# Balance_batt_protection.net
KiCad netlist of a schematic drawn in Altium Designer
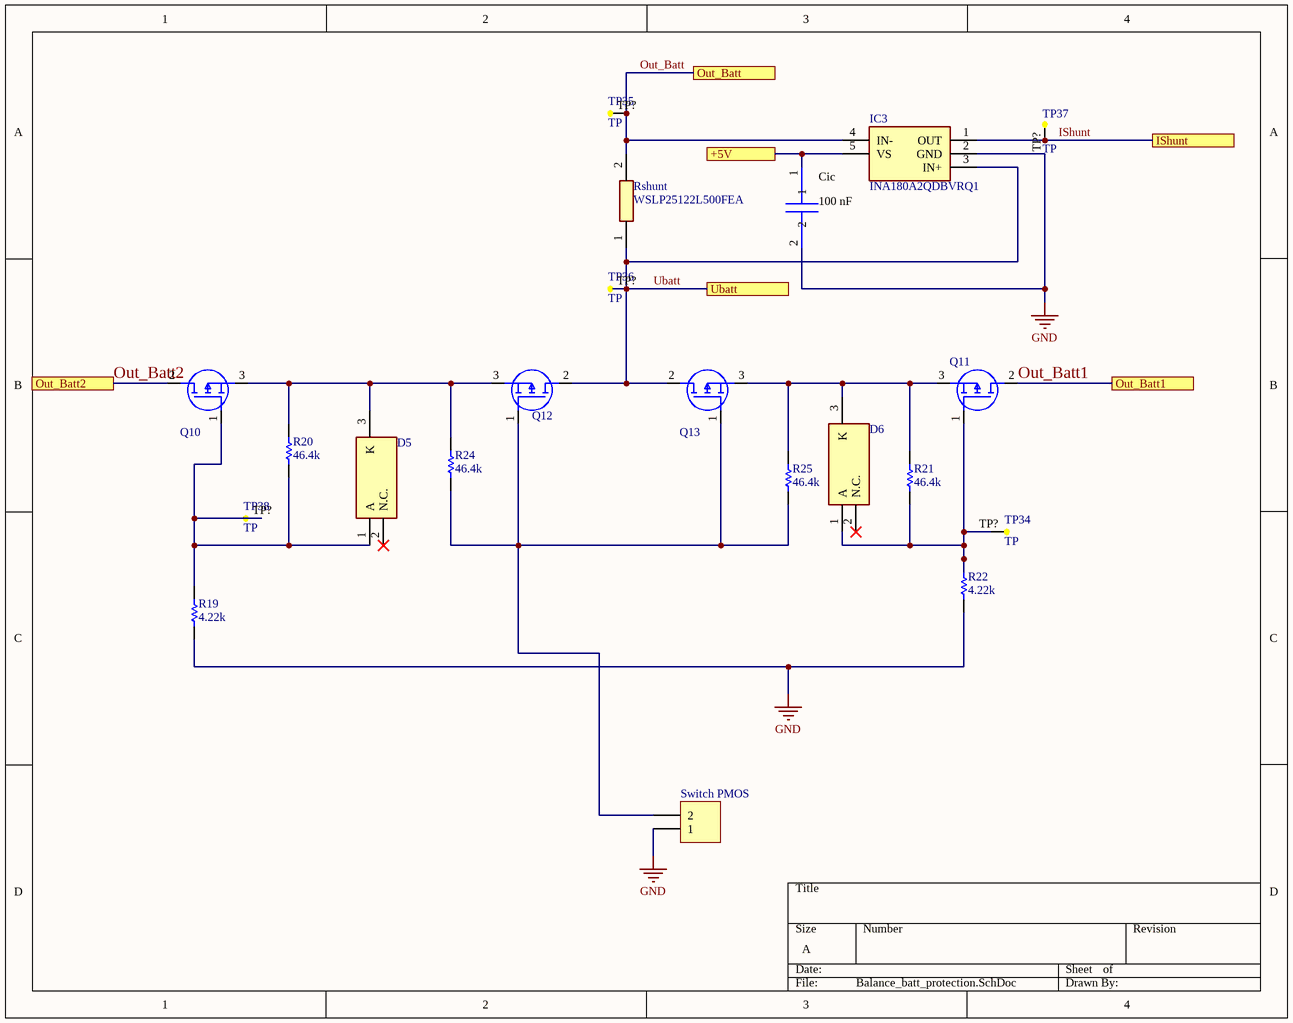
[diagram p0: Balance_batt_protection.SchDoc]

(export (version "E")
  (design (tool "Eeschema 10.0.6"))
  (components
    (comp (ref "Cic")
      (value "100 nF")
      (footprint "CAPC1005X55N")
      (description "C3216X6S1V106K16")
      (fields
        (field (name "MANUFACTURER PART NUMBER") "C3216X6S1V106K160AC")
        (field (name "Comment") "C2012X7S1C106K")
      )
      (libsource (lib "TI WEBENCH") (part "Cin"))
    )
    (comp (ref "D5")
      (value "SZBZX84C18ET1G")
      (footprint "SOT95P230X110-3N")
      (description "Zener Diode")
      (fields
        (field (name "MANUFACTURER_PART_NUMBER") "BZX84W-C15F")
        (field (name "MOUSER PART NUMBER") "771-BZX84W-C15F")
      )
      (libsource (lib "BZX84(sot 23)") (part "BZX84W-C15F"))
    )
    (comp (ref "D6")
      (value "SZBZX84C18ET1G")
      (footprint "SOT95P230X110-3N")
      (description "Zener Diode")
      (fields
        (field (name "MANUFACTURER_PART_NUMBER") "BZX84W-C15F")
        (field (name "MOUSER PART NUMBER") "771-BZX84W-C15F")
      )
      (libsource (lib "BZX84(sot 23)") (part "BZX84W-C15F"))
    )
    (comp (ref "IC3")
      (value "INA180A2QDBVRQ1")
      (footprint "SOT95P280X145-5N")
      (description "Attenuator or Isolator")
      (fields (field (name "MOUSER PART NUMBER") "595-INA180A2QDBVRQ1"))
      (libsource (lib "INA180A2QDBVRQ1") (part "INA180A2QDBVRQ1"))
    )
    (comp (ref "Q10")
      (value "SQD50P04-09L_GE3")
      (footprint "SamacSys:SQD50P0409L_GE3")
      (description "MOSFET (P-Channel)")
      (fields (field (name "MOUSER PART NUMBER") "78-SQD50P04-09L_GE3"))
      (libsource (lib "SQD50P04-09L_GE3(TO252)") (part "SQD50P04-09L_GE3"))
    )
    (comp (ref "Q11")
      (value "SQD50P04-09L_GE3")
      (footprint "SamacSys:SQD50P0409L_GE3")
      (description "MOSFET (P-Channel)")
      (fields (field (name "MOUSER PART NUMBER") "78-SQD50P04-09L_GE3"))
      (libsource (lib "SQD50P04-09L_GE3(TO252)") (part "SQD50P04-09L_GE3"))
    )
    (comp (ref "Q12")
      (value "SQD50P04-09L_GE3")
      (footprint "SQD50P0409L_GE3")
      (description "MOSFET (P-Channel)")
      (fields (field (name "MOUSER PART NUMBER") "78-SQD50P04-09L_GE3"))
      (libsource (lib "SQD50P04-09L_GE3(TO252)") (part "SQD50P04-09L_GE3"))
    )
    (comp (ref "Q13")
      (value "SQD50P04-09L_GE3")
      (footprint "SQD50P0409L_GE3")
      (description "MOSFET (P-Channel)")
      (fields (field (name "MOUSER PART NUMBER") "78-SQD50P04-09L_GE3"))
      (libsource (lib "SQD50P04-09L_GE3(TO252)") (part "SQD50P04-09L_GE3"))
    )
    (comp (ref "R19")
      (value "4.22k")
      (footprint "ERJP06D1000V")
      (description "Resistor")
      (fields (field (name "Comment") "MCR03..PFX1002") (field (name "PUBLISHER") "Altium Limited"))
      (libsource (lib "Miscellaneous Devices") (part "Res1"))
    )
    (comp (ref "R20")
      (value "46.4k")
      (footprint "RESC1608X55N")
      (description "Resistor")
      (fields (field (name "Comment") "MCR03..PFX1002") (field (name "PUBLISHER") "Altium Limited"))
      (libsource (lib "Miscellaneous Devices") (part "Res1"))
    )
    (comp (ref "R21")
      (value "46.4k")
      (footprint "RESC1608X55N")
      (description "Resistor")
      (fields (field (name "Comment") "MCR03..PFX1002") (field (name "PUBLISHER") "Altium Limited"))
      (libsource (lib "Miscellaneous Devices") (part "Res1"))
    )
    (comp (ref "R22")
      (value "4.22k")
      (footprint "ERJP06D1000V")
      (description "Resistor")
      (fields (field (name "Comment") "MCR03..PFX1002") (field (name "PUBLISHER") "Altium Limited"))
      (libsource (lib "Miscellaneous Devices") (part "Res1"))
    )
    (comp (ref "R24")
      (value "46.4k")
      (footprint "RESC1608X55N")
      (description "Resistor")
      (fields (field (name "Comment") "MCR03..PFX1002") (field (name "PUBLISHER") "Altium Limited"))
      (libsource (lib "Miscellaneous Devices") (part "Res1"))
    )
    (comp (ref "R25")
      (value "46.4k")
      (footprint "RESC1608X55N")
      (description "Resistor")
      (fields (field (name "Comment") "MCR03..PFX1002") (field (name "PUBLISHER") "Altium Limited"))
      (libsource (lib "Miscellaneous Devices") (part "Res1"))
    )
    (comp (ref "Rshunt")
      (value "WSLP25122L500FEA")
      (footprint "RESC6432X89N")
      (description "Resistor")
      (fields (field (name "MOUSER PART NUMBER") "71-WSLP25122L500FEA"))
      (libsource (lib "WSLP25122L000FEA") (part "WSLP25122L500FEA"))
    )
    (comp (ref "Switch PMOS")
      (value "5V")
      (footprint "TB002V50002BE")
      (description "Header, 2-Pin")
      (fields (field (name "PUBLISHER") "Altium Limited"))
      (libsource (lib "Miscellaneous Connectors") (part "Header 2"))
    )
    (comp (ref "TP34")
      (value "TP")
      (footprint "Test_Point0.5x0.5")
      (libsource (lib "TP_0.6x0.6") (part "TEst_Point_0.5x0.5"))
    )
    (comp (ref "TP35")
      (value "TP")
      (footprint "Test_Point0.5x0.5")
      (libsource (lib "TP_0.6x0.6") (part "TEst_Point_0.5x0.5"))
    )
    (comp (ref "TP36")
      (value "TP")
      (footprint "Test_Point0.5x0.5")
      (libsource (lib "TP_0.6x0.6") (part "TEst_Point_0.5x0.5"))
    )
    (comp (ref "TP37")
      (value "TP")
      (footprint "Test_Point0.5x0.5")
      (libsource (lib "TP_0.6x0.6") (part "TEst_Point_0.5x0.5"))
    )
    (comp (ref "TP38")
      (value "TP")
      (footprint "Test_Point0.5x0.5")
      (libsource (lib "TP_0.6x0.6") (part "TEst_Point_0.5x0.5"))
    )
  )
  (nets
    (net (code "1") (name "/+5V") (class "Default")
      (node (ref "Cic") (pin "1") (pinfunction "1_1") (pintype "passive"))
      (node (ref "IC3") (pin "5") (pinfunction "VS_5") (pintype "power_in"))
    )
    (net (code "2") (name "/IShunt") (class "Default")
      (node (ref "IC3") (pin "1") (pinfunction "OUT_1") (pintype "power_in"))
      (node (ref "TP37") (pin "TP?") (pinfunction "TP_TP?") (pintype "passive"))
    )
    (net (code "3") (name "/Out_Batt") (class "Default")
      (node (ref "IC3") (pin "4") (pinfunction "IN-_4") (pintype "power_in"))
      (node (ref "Rshunt") (pin "2") (pinfunction "2_2") (pintype "passive"))
      (node (ref "TP35") (pin "TP?") (pinfunction "TP_TP?") (pintype "passive"))
    )
    (net (code "4") (name "/Out_Batt1") (class "Default")
      (node (ref "Q11") (pin "2") (pinfunction "D_2") (pintype "passive"))
    )
    (net (code "5") (name "/Out_Batt2") (class "Default")
      (node (ref "Q10") (pin "2") (pinfunction "D_2") (pintype "passive"))
    )
    (net (code "6") (name "/Ubatt") (class "Default")
      (node (ref "IC3") (pin "3") (pinfunction "IN+_3") (pintype "power_in"))
      (node (ref "Q12") (pin "2") (pinfunction "D_2") (pintype "passive"))
      (node (ref "Q13") (pin "2") (pinfunction "D_2") (pintype "passive"))
      (node (ref "Rshunt") (pin "1") (pinfunction "1_1") (pintype "passive"))
      (node (ref "TP36") (pin "TP?") (pinfunction "TP_TP?") (pintype "passive"))
    )
    (net (code "7") (name "GND") (class "Default")
      (node (ref "Cic") (pin "2") (pinfunction "2_2") (pintype "passive"))
      (node (ref "IC3") (pin "2") (pinfunction "GND_2") (pintype "power_in"))
      (node (ref "R19") (pin "2") (pinfunction "2_2") (pintype "passive"))
      (node (ref "R22") (pin "2") (pinfunction "2_2") (pintype "passive"))
      (node (ref "Switch PMOS") (pin "1") (pinfunction "1_1") (pintype "passive"))
    )
    (net (code "8") (name "Net-(D5-A)") (class "Default")
      (node (ref "D5") (pin "1") (pinfunction "A_1") (pintype "passive"))
      (node (ref "Q10") (pin "1") (pinfunction "G_1") (pintype "passive"))
      (node (ref "R19") (pin "1") (pinfunction "1_1") (pintype "passive"))
      (node (ref "R20") (pin "2") (pinfunction "2_2") (pintype "passive"))
      (node (ref "TP38") (pin "TP?") (pinfunction "TP_TP?") (pintype "passive"))
    )
    (net (code "9") (name "Net-(D5-K)") (class "Default")
      (node (ref "D5") (pin "3") (pinfunction "K_3") (pintype "passive"))
      (node (ref "Q10") (pin "3") (pinfunction "S_3") (pintype "passive"))
      (node (ref "Q12") (pin "3") (pinfunction "S_3") (pintype "passive"))
      (node (ref "R20") (pin "1") (pinfunction "1_1") (pintype "passive"))
      (node (ref "R24") (pin "1") (pinfunction "1_1") (pintype "passive"))
    )
    (net (code "10") (name "Net-(D6-A)") (class "Default")
      (node (ref "D6") (pin "1") (pinfunction "A_1") (pintype "passive"))
      (node (ref "Q11") (pin "1") (pinfunction "G_1") (pintype "passive"))
      (node (ref "R21") (pin "2") (pinfunction "2_2") (pintype "passive"))
      (node (ref "R22") (pin "1") (pinfunction "1_1") (pintype "passive"))
      (node (ref "TP34") (pin "TP?") (pinfunction "TP_TP?") (pintype "passive"))
    )
    (net (code "11") (name "Net-(D6-K)") (class "Default")
      (node (ref "D6") (pin "3") (pinfunction "K_3") (pintype "passive"))
      (node (ref "Q11") (pin "3") (pinfunction "S_3") (pintype "passive"))
      (node (ref "Q13") (pin "3") (pinfunction "S_3") (pintype "passive"))
      (node (ref "R21") (pin "1") (pinfunction "1_1") (pintype "passive"))
      (node (ref "R25") (pin "1") (pinfunction "1_1") (pintype "passive"))
    )
    (net (code "12") (name "Net-(Q12-G)") (class "Default")
      (node (ref "Q12") (pin "1") (pinfunction "G_1") (pintype "passive"))
      (node (ref "Q13") (pin "1") (pinfunction "G_1") (pintype "passive"))
      (node (ref "R24") (pin "2") (pinfunction "2_2") (pintype "passive"))
      (node (ref "R25") (pin "2") (pinfunction "2_2") (pintype "passive"))
      (node (ref "Switch PMOS") (pin "2") (pinfunction "2_2") (pintype "passive"))
    )
    (net (code "13") (name "unconnected-(D5-N.C.-Pad2)") (class "Default")
      (node (ref "D5") (pin "2") (pinfunction "N.C._2") (pintype "passive+no_connect"))
    )
    (net (code "14") (name "unconnected-(D6-N.C.-Pad2)") (class "Default")
      (node (ref "D6") (pin "2") (pinfunction "N.C._2") (pintype "passive+no_connect"))
    )
  )
)
